# fg.net
KiCad netlist of a schematic drawn in EAGLE
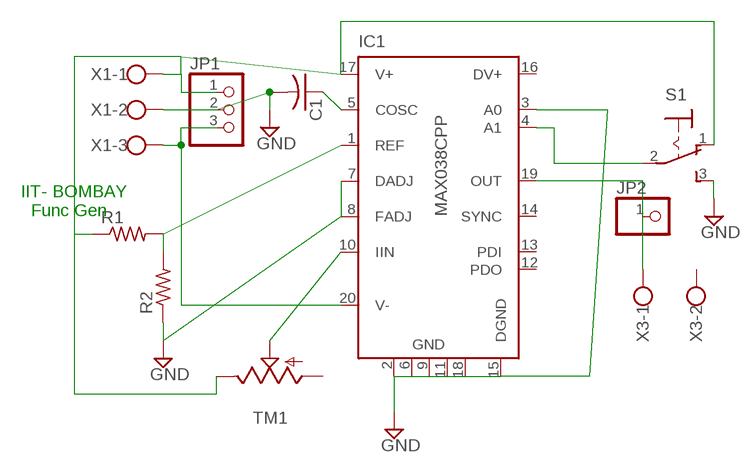
[diagram p0: schematic, sheet 1]

(export (version "E")
  (design (tool "Eeschema 10.0.6"))
  (components
    (comp (ref "C1")
      (value "C-US050-045X075")
      (footprint "eagle-import:C050-045X075")
      (libsource (lib "eagle-import") (part "C-US050-045X075"))
    )
    (comp (ref "IC1")
      (value "MAX038CPP")
      (footprint "eagle-import:DIL20")
      (libsource (lib "eagle-import") (part "MAX038PPC"))
    )
    (comp (ref "JP1")
      (value "PINHD-1X3CB")
      (footprint "eagle-import:1X03-CLEANBIG")
      (libsource (lib "eagle-import") (part "PINHD-1X3CB"))
    )
    (comp (ref "JP2")
      (value "PINHD-1X1CB")
      (footprint "eagle-import:1X01-CLEANBIG")
      (libsource (lib "eagle-import") (part "PINHD-1X1CB"))
    )
    (comp (ref "R1")
      (value "R-US_0309/10")
      (footprint "eagle-import:0309_10")
      (libsource (lib "eagle-import") (part "R-US_0309/10"))
    )
    (comp (ref "R2")
      (value "R-US_0309/10")
      (footprint "eagle-import:0309_10")
      (libsource (lib "eagle-import") (part "R-US_0309/10"))
    )
    (comp (ref "S1")
      (value "320-916")
      (footprint "eagle-import:320-916")
      (libsource (lib "eagle-import") (part "320-916"))
    )
    (comp (ref "TM1")
      (value "TRIM")
      (footprint "eagle-import:6MM")
      (libsource (lib "eagle-import") (part "TRIM"))
    )
    (comp (ref "X1")
      (value "W237-103")
      (footprint "eagle-import:W237-103")
      (fields (field (name "MPN") "237-103"))
      (libsource (lib "eagle-import") (part "W237-103"))
    )
    (comp (ref "X3")
      (value "W237-102")
      (footprint "eagle-import:W237-102")
      (fields (field (name "MPN") "237-102"))
      (libsource (lib "eagle-import") (part "W237-102"))
    )
  )
  (nets
    (net (code "1") (name "/DV+") (class "Default")
      (node (ref "IC1") (pin "16") (pinfunction "DV+_16") (pintype "power_in"))
    )
    (net (code "2") (name "GND") (class "Default")
      (node (ref "C1") (pin "2") (pinfunction "2_2") (pintype "passive"))
      (node (ref "IC1") (pin "11") (pinfunction "GND_11") (pintype "power_in"))
      (node (ref "IC1") (pin "15") (pinfunction "DGND_15") (pintype "power_in"))
      (node (ref "IC1") (pin "18") (pinfunction "GND_18") (pintype "power_in"))
      (node (ref "IC1") (pin "2") (pinfunction "GND_2") (pintype "power_in"))
      (node (ref "IC1") (pin "3") (pinfunction "A0_3") (pintype "input"))
      (node (ref "IC1") (pin "6") (pinfunction "GND_6") (pintype "power_in"))
      (node (ref "IC1") (pin "7") (pinfunction "DADJ_7") (pintype "input"))
      (node (ref "IC1") (pin "8") (pinfunction "FADJ_8") (pintype "input"))
      (node (ref "IC1") (pin "9") (pinfunction "GND_9") (pintype "power_in"))
      (node (ref "JP1") (pin "2") (pinfunction "2_2") (pintype "passive"))
      (node (ref "R2") (pin "1") (pinfunction "1_1") (pintype "passive"))
      (node (ref "S1") (pin "3") (pinfunction "S_3") (pintype "passive"))
      (node (ref "X1") (pin "2") (pinfunction "KL_2") (pintype "passive"))
    )
    (net (code "3") (name "Net-(IC1-A1)") (class "Default")
      (node (ref "IC1") (pin "4") (pinfunction "A1_4") (pintype "input"))
      (node (ref "S1") (pin "2") (pinfunction "P_2") (pintype "passive"))
    )
    (net (code "4") (name "Net-(IC1-COSC)") (class "Default")
      (node (ref "C1") (pin "1") (pinfunction "1_1") (pintype "passive"))
      (node (ref "IC1") (pin "5") (pinfunction "COSC_5") (pintype "passive"))
    )
    (net (code "5") (name "Net-(IC1-IIN)") (class "Default")
      (node (ref "IC1") (pin "10") (pinfunction "IIN_10") (pintype "passive"))
      (node (ref "TM1") (pin "S") (pinfunction "S_S") (pintype "passive"))
    )
    (net (code "6") (name "Net-(IC1-OUT)") (class "Default")
      (node (ref "IC1") (pin "19") (pinfunction "OUT_19") (pintype "output"))
      (node (ref "JP2") (pin "1") (pinfunction "1_1") (pintype "passive"))
      (node (ref "X3") (pin "1") (pinfunction "KL_1") (pintype "passive"))
    )
    (net (code "7") (name "Net-(IC1-REF)") (class "Default")
      (node (ref "IC1") (pin "1") (pinfunction "REF_1") (pintype "output"))
      (node (ref "R1") (pin "2") (pinfunction "2_2") (pintype "passive"))
      (node (ref "R2") (pin "2") (pinfunction "2_2") (pintype "passive"))
    )
    (net (code "8") (name "Net-(IC1-V+)") (class "Default")
      (node (ref "IC1") (pin "17") (pinfunction "V+_17") (pintype "power_in"))
      (node (ref "JP1") (pin "1") (pinfunction "1_1") (pintype "passive"))
      (node (ref "R1") (pin "1") (pinfunction "1_1") (pintype "passive"))
      (node (ref "S1") (pin "1") (pinfunction "O_1") (pintype "passive"))
      (node (ref "TM1") (pin "E") (pinfunction "E_E") (pintype "passive"))
      (node (ref "X1") (pin "1") (pinfunction "KL_1") (pintype "passive"))
    )
    (net (code "9") (name "Net-(IC1-V-)") (class "Default")
      (node (ref "IC1") (pin "20") (pinfunction "V-_20") (pintype "power_in"))
      (node (ref "JP1") (pin "3") (pinfunction "3_3") (pintype "passive"))
      (node (ref "X1") (pin "3") (pinfunction "KL_3") (pintype "passive"))
    )
    (net (code "10") (name "unconnected-(IC1-PDI-Pad13)") (class "Default")
      (node (ref "IC1") (pin "13") (pinfunction "PDI_13") (pintype "input"))
    )
    (net (code "11") (name "unconnected-(IC1-PDO-Pad12)") (class "Default")
      (node (ref "IC1") (pin "12") (pinfunction "PDO_12") (pintype "output"))
    )
    (net (code "12") (name "unconnected-(IC1-SYNC-Pad14)") (class "Default")
      (node (ref "IC1") (pin "14") (pinfunction "SYNC_14") (pintype "output"))
    )
    (net (code "13") (name "unconnected-(TM1-PadA)") (class "Default")
      (node (ref "TM1") (pin "A") (pinfunction "A_A") (pintype "passive"))
    )
    (net (code "14") (name "unconnected-(X3B-KL-Pad2)") (class "Default")
      (node (ref "X3") (pin "2") (pinfunction "KL_2") (pintype "passive"))
    )
  )
)
